# ATMEGA328PUTQFP_SMD_0603.net
KiCad netlist of a schematic drawn in EAGLE
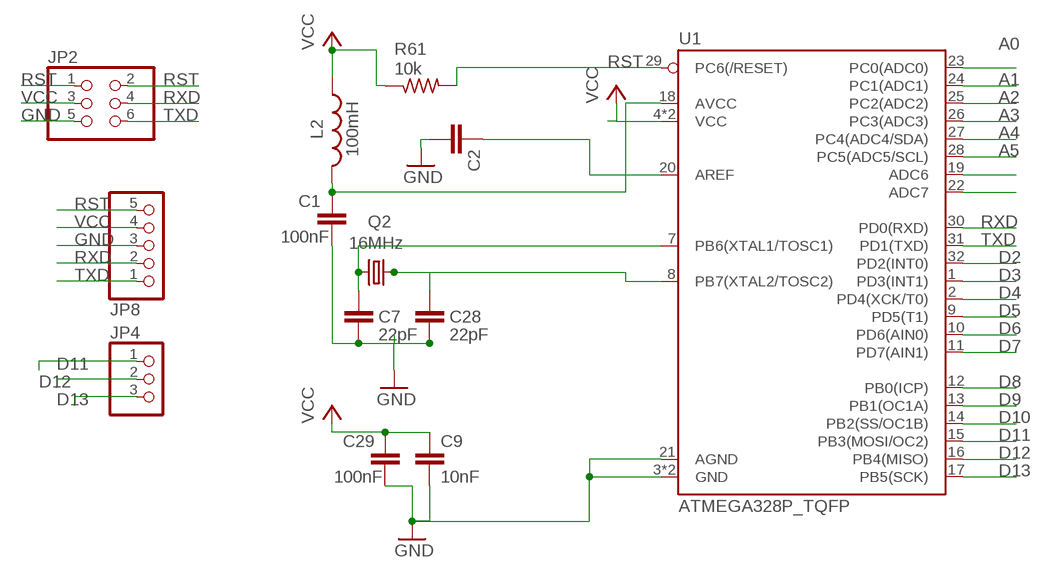
[diagram p0: schematic, sheet 1]

(export (version "E")
  (design (tool "Eeschema 10.0.6"))
  (components
    (comp (ref "C1")
      (value "100nF")
      (footprint "eagle-import:C0603")
      (libsource (lib "eagle-import") (part "C-EUC0603"))
    )
    (comp (ref "C2")
      (value "C-EUC0603")
      (footprint "eagle-import:C0603")
      (libsource (lib "eagle-import") (part "C-EUC0603"))
    )
    (comp (ref "C7")
      (value "22pF")
      (footprint "eagle-import:C0603")
      (libsource (lib "eagle-import") (part "C-EUC0603"))
    )
    (comp (ref "C9")
      (value "10nF")
      (footprint "eagle-import:C0603")
      (libsource (lib "eagle-import") (part "C-EUC0603"))
    )
    (comp (ref "C28")
      (value "22pF")
      (footprint "eagle-import:C0603")
      (libsource (lib "eagle-import") (part "C-EUC0603"))
    )
    (comp (ref "C29")
      (value "100nF")
      (footprint "eagle-import:C0603")
      (libsource (lib "eagle-import") (part "C-EUC0603"))
    )
    (comp (ref "JP2")
      (value "PINHD-2X3")
      (footprint "eagle-import:2X03")
      (libsource (lib "eagle-import") (part "PINHD-2X3"))
    )
    (comp (ref "JP4")
      (value "PINHD-1X3")
      (footprint "eagle-import:1X03")
      (libsource (lib "eagle-import") (part "PINHD-1X3"))
    )
    (comp (ref "JP8")
      (value "PINHD-1X5/90")
      (footprint "eagle-import:1X05_90")
      (libsource (lib "eagle-import") (part "PINHD-1X5/90"))
    )
    (comp (ref "L2")
      (value "100mH")
      (footprint "eagle-import:L0603")
      (libsource (lib "eagle-import") (part "L-USL0603"))
    )
    (comp (ref "Q2")
      (value "16MHz")
      (footprint "eagle-import:CRYSTAL-SMD-5X3.2-4PAD")
      (libsource (lib "eagle-import") (part "CRYSTAL-16MHZSMD-5X3.2"))
    )
    (comp (ref "R61")
      (value "10k")
      (footprint "eagle-import:R0603")
      (libsource (lib "eagle-import") (part "R-US_R0603"))
    )
    (comp (ref "U1")
      (value "ATMEGA328P_TQFP")
      (footprint "eagle-import:TQFP32-08")
      (libsource (lib "eagle-import") (part "ATMEGA328P_TQFP"))
    )
  )
  (nets
    (net (code "1") (name "/A0") (class "Default")
      (node (ref "U1") (pin "23") (pinfunction "PC0(ADC0)_23") (pintype "bidirectional"))
    )
    (net (code "2") (name "/A1") (class "Default")
      (node (ref "U1") (pin "24") (pinfunction "PC1(ADC1)_24") (pintype "bidirectional"))
    )
    (net (code "3") (name "/A2") (class "Default")
      (node (ref "U1") (pin "25") (pinfunction "PC2(ADC2)_25") (pintype "bidirectional"))
    )
    (net (code "4") (name "/A3") (class "Default")
      (node (ref "U1") (pin "26") (pinfunction "PC3(ADC3)_26") (pintype "bidirectional"))
    )
    (net (code "5") (name "/A4") (class "Default")
      (node (ref "U1") (pin "27") (pinfunction "PC4(ADC4/SDA)_27") (pintype "bidirectional"))
    )
    (net (code "6") (name "/A5") (class "Default")
      (node (ref "U1") (pin "28") (pinfunction "PC5(ADC5/SCL)_28") (pintype "bidirectional"))
    )
    (net (code "7") (name "/D2") (class "Default")
      (node (ref "U1") (pin "32") (pinfunction "PD2(INT0)_32") (pintype "bidirectional"))
    )
    (net (code "8") (name "/D3") (class "Default")
      (node (ref "U1") (pin "1") (pinfunction "PD3(INT1)_1") (pintype "bidirectional"))
    )
    (net (code "9") (name "/D4") (class "Default")
      (node (ref "U1") (pin "2") (pinfunction "PD4(XCK/T0)_2") (pintype "bidirectional"))
    )
    (net (code "10") (name "/D5") (class "Default")
      (node (ref "U1") (pin "9") (pinfunction "PD5(T1)_9") (pintype "bidirectional"))
    )
    (net (code "11") (name "/D6") (class "Default")
      (node (ref "U1") (pin "10") (pinfunction "PD6(AIN0)_10") (pintype "bidirectional"))
    )
    (net (code "12") (name "/D7") (class "Default")
      (node (ref "U1") (pin "11") (pinfunction "PD7(AIN1)_11") (pintype "bidirectional"))
    )
    (net (code "13") (name "/D8") (class "Default")
      (node (ref "U1") (pin "12") (pinfunction "PB0(ICP)_12") (pintype "bidirectional"))
    )
    (net (code "14") (name "/D9") (class "Default")
      (node (ref "U1") (pin "13") (pinfunction "PB1(OC1A)_13") (pintype "bidirectional"))
    )
    (net (code "15") (name "/D10") (class "Default")
      (node (ref "U1") (pin "14") (pinfunction "PB2(SS/OC1B)_14") (pintype "bidirectional"))
    )
    (net (code "16") (name "/D11") (class "Default")
      (node (ref "JP4") (pin "1") (pinfunction "1_1") (pintype "passive"))
      (node (ref "U1") (pin "15") (pinfunction "PB3(MOSI/OC2)_15") (pintype "bidirectional"))
    )
    (net (code "17") (name "/D12") (class "Default")
      (node (ref "JP4") (pin "2") (pinfunction "2_2") (pintype "passive"))
      (node (ref "U1") (pin "16") (pinfunction "PB4(MISO)_16") (pintype "bidirectional"))
    )
    (net (code "18") (name "/D13") (class "Default")
      (node (ref "JP4") (pin "3") (pinfunction "3_3") (pintype "passive"))
      (node (ref "U1") (pin "17") (pinfunction "PB5(SCK)_17") (pintype "bidirectional"))
    )
    (net (code "19") (name "/RST") (class "Default")
      (node (ref "JP2") (pin "1") (pinfunction "1_1") (pintype "passive"))
      (node (ref "JP2") (pin "2") (pinfunction "2_2") (pintype "passive"))
      (node (ref "JP8") (pin "5") (pinfunction "5_5") (pintype "passive"))
      (node (ref "R61") (pin "2") (pinfunction "2_2") (pintype "passive"))
      (node (ref "U1") (pin "29") (pinfunction "PC6(/RESET)_29") (pintype "bidirectional"))
    )
    (net (code "20") (name "/RXD") (class "Default")
      (node (ref "JP2") (pin "4") (pinfunction "4_4") (pintype "passive"))
      (node (ref "JP8") (pin "2") (pinfunction "2_2") (pintype "passive"))
      (node (ref "U1") (pin "30") (pinfunction "PD0(RXD)_30") (pintype "bidirectional"))
    )
    (net (code "21") (name "/TXD") (class "Default")
      (node (ref "JP2") (pin "6") (pinfunction "6_6") (pintype "passive"))
      (node (ref "JP8") (pin "1") (pinfunction "1_1") (pintype "passive"))
      (node (ref "U1") (pin "31") (pinfunction "PD1(TXD)_31") (pintype "bidirectional"))
    )
    (net (code "22") (name "GND") (class "Default")
      (node (ref "C1") (pin "2") (pinfunction "2_2") (pintype "passive"))
      (node (ref "C2") (pin "2") (pinfunction "2_2") (pintype "passive"))
      (node (ref "C28") (pin "2") (pinfunction "2_2") (pintype "passive"))
      (node (ref "C29") (pin "2") (pinfunction "2_2") (pintype "passive"))
      (node (ref "C7") (pin "2") (pinfunction "2_2") (pintype "passive"))
      (node (ref "C9") (pin "2") (pinfunction "2_2") (pintype "passive"))
      (node (ref "JP2") (pin "5") (pinfunction "5_5") (pintype "passive"))
      (node (ref "JP8") (pin "3") (pinfunction "3_3") (pintype "passive"))
      (node (ref "U1") (pin "21") (pinfunction "AGND_21") (pintype "bidirectional"))
      (node (ref "U1") (pin "3") (pinfunction "GND_3") (pintype "bidirectional"))
      (node (ref "U1") (pin "5") (pinfunction "GND_5") (pintype "bidirectional"))
    )
    (net (code "23") (name "Net-(Q2-2)") (class "Default")
      (node (ref "C7") (pin "1") (pinfunction "1_1") (pintype "passive"))
      (node (ref "Q2") (pin "3") (pinfunction "2_3") (pintype "passive"))
      (node (ref "U1") (pin "7") (pinfunction "PB6(XTAL1/TOSC1)_7") (pintype "bidirectional"))
    )
    (net (code "24") (name "Net-(U1-AREF)") (class "Default")
      (node (ref "C2") (pin "1") (pinfunction "1_1") (pintype "passive"))
      (node (ref "U1") (pin "20") (pinfunction "AREF_20") (pintype "bidirectional"))
    )
    (net (code "25") (name "Net-(U1-AVCC)") (class "Default")
      (node (ref "C1") (pin "1") (pinfunction "1_1") (pintype "passive"))
      (node (ref "L2") (pin "2") (pinfunction "2_2") (pintype "passive"))
      (node (ref "U1") (pin "18") (pinfunction "AVCC_18") (pintype "bidirectional"))
    )
    (net (code "26") (name "Net-(U1-PB7(XTAL2{slash}TOSC2))") (class "Default")
      (node (ref "C28") (pin "1") (pinfunction "1_1") (pintype "passive"))
      (node (ref "Q2") (pin "1") (pinfunction "1_1") (pintype "passive"))
      (node (ref "U1") (pin "8") (pinfunction "PB7(XTAL2/TOSC2)_8") (pintype "bidirectional"))
    )
    (net (code "27") (name "VCC") (class "Default")
      (node (ref "C29") (pin "1") (pinfunction "1_1") (pintype "passive"))
      (node (ref "C9") (pin "1") (pinfunction "1_1") (pintype "passive"))
      (node (ref "JP2") (pin "3") (pinfunction "3_3") (pintype "passive"))
      (node (ref "JP8") (pin "4") (pinfunction "4_4") (pintype "passive"))
      (node (ref "L2") (pin "1") (pinfunction "1_1") (pintype "passive"))
      (node (ref "R61") (pin "1") (pinfunction "1_1") (pintype "passive"))
      (node (ref "U1") (pin "4") (pinfunction "VCC_4") (pintype "bidirectional"))
      (node (ref "U1") (pin "6") (pinfunction "VCC_6") (pintype "bidirectional"))
    )
    (net (code "28") (name "unconnected-(U1-ADC6-Pad19)") (class "Default")
      (node (ref "U1") (pin "19") (pinfunction "ADC6_19") (pintype "bidirectional"))
    )
    (net (code "29") (name "unconnected-(U1-ADC7-Pad22)") (class "Default")
      (node (ref "U1") (pin "22") (pinfunction "ADC7_22") (pintype "bidirectional"))
    )
  )
)
